# FTS_V1_0.net
KiCad netlist of a schematic drawn in EAGLE
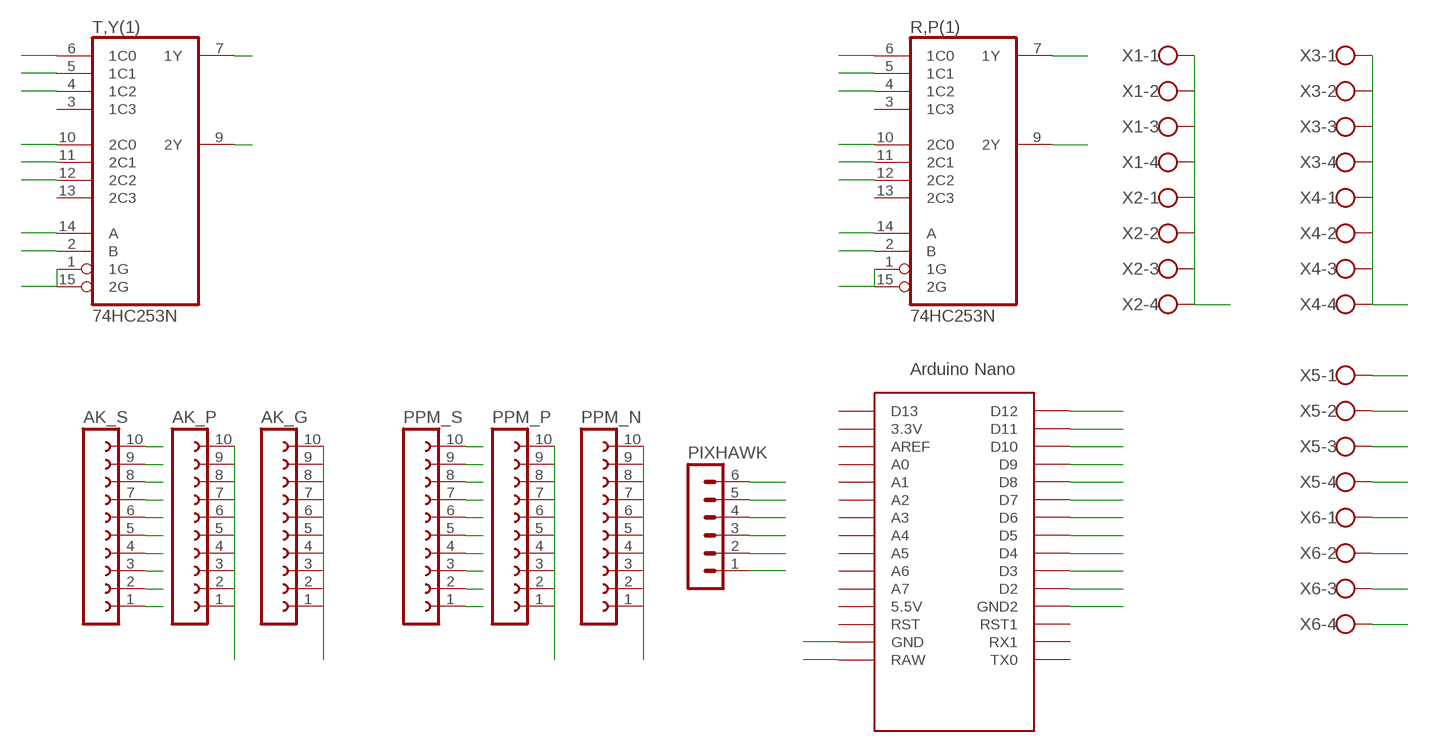
[diagram p0: schematic, sheet 1]

(export (version "E")
  (design (tool "Eeschema 10.0.6"))
  (components
    (comp (ref "AK_G")
      (value "FE10-1")
      (footprint "eagle-import:FE10")
      (libsource (lib "eagle-import") (part "FE10-1"))
    )
    (comp (ref "AK_P")
      (value "FE10-1")
      (footprint "eagle-import:FE10")
      (libsource (lib "eagle-import") (part "FE10-1"))
    )
    (comp (ref "AK_S")
      (value "FE10-1")
      (footprint "eagle-import:FE10")
      (libsource (lib "eagle-import") (part "FE10-1"))
    )
    (comp (ref "PIXHAWK")
      (value "MA06-1")
      (footprint "eagle-import:MA06-1")
      (libsource (lib "eagle-import") (part "MA06-1"))
    )
    (comp (ref "PPM_N")
      (value "FE10-1")
      (footprint "eagle-import:FE10")
      (libsource (lib "eagle-import") (part "FE10-1"))
    )
    (comp (ref "PPM_P")
      (value "FE10-1")
      (footprint "eagle-import:FE10")
      (libsource (lib "eagle-import") (part "FE10-1"))
    )
    (comp (ref "PPM_S")
      (value "FE10-1")
      (footprint "eagle-import:FE10")
      (libsource (lib "eagle-import") (part "FE10-1"))
    )
    (comp (ref "R,P(1)")
      (value "74HC253N")
      (footprint "eagle-import:DIL16")
      (libsource (lib "eagle-import") (part "74253NHC"))
    )
    (comp (ref "T,Y(1)")
      (value "74HC253N")
      (footprint "eagle-import:DIL16")
      (libsource (lib "eagle-import") (part "74253NHC"))
    )
    (comp (ref "U$1")
      (value "NANO")
      (footprint "eagle-import:NANO")
      (libsource (lib "eagle-import") (part "NANO"))
    )
    (comp (ref "X1")
      (value "W237-4")
      (footprint "eagle-import:W237-4")
      (libsource (lib "eagle-import") (part "W237-4"))
    )
    (comp (ref "X2")
      (value "W237-4")
      (footprint "eagle-import:W237-4")
      (libsource (lib "eagle-import") (part "W237-4"))
    )
    (comp (ref "X3")
      (value "W237-4")
      (footprint "eagle-import:W237-4")
      (libsource (lib "eagle-import") (part "W237-4"))
    )
    (comp (ref "X4")
      (value "W237-4")
      (footprint "eagle-import:W237-4")
      (libsource (lib "eagle-import") (part "W237-4"))
    )
    (comp (ref "X5")
      (value "W237-4")
      (footprint "eagle-import:W237-4")
      (libsource (lib "eagle-import") (part "W237-4"))
    )
    (comp (ref "X6")
      (value "W237-4")
      (footprint "eagle-import:W237-4")
      (libsource (lib "eagle-import") (part "W237-4"))
    )
  )
  (nets
    (net (code "1") (name "/AUX2") (class "Default")
      (node (ref "AK_S") (pin "7") (pinfunction "7_7") (pintype "passive"))
      (node (ref "U$1") (pin "D4") (pinfunction "D4_D4") (pintype "bidirectional"))
    )
    (net (code "2") (name "/DROP") (class "Default")
      (node (ref "AK_S") (pin "10") (pinfunction "10_10") (pintype "passive"))
      (node (ref "X6") (pin "4") (pinfunction "KL_4") (pintype "passive"))
    )
    (net (code "3") (name "/FTS-P") (class "Default")
      (node (ref "R,P(1)") (pin "12") (pinfunction "2C2_12") (pintype "input"))
      (node (ref "U$1") (pin "D10") (pinfunction "D10_D10") (pintype "bidirectional"))
    )
    (net (code "4") (name "/FTS-R") (class "Default")
      (node (ref "R,P(1)") (pin "4") (pinfunction "1C2_4") (pintype "input"))
      (node (ref "U$1") (pin "D9") (pinfunction "D9_D9") (pintype "bidirectional"))
    )
    (net (code "5") (name "/FTS-T") (class "Default")
      (node (ref "T,Y(1)") (pin "4") (pinfunction "1C2_4") (pintype "input"))
      (node (ref "U$1") (pin "D11") (pinfunction "D11_D11") (pintype "bidirectional"))
    )
    (net (code "6") (name "/FTS-Y") (class "Default")
      (node (ref "T,Y(1)") (pin "12") (pinfunction "2C2_12") (pintype "input"))
      (node (ref "U$1") (pin "D6") (pinfunction "D6_D6") (pintype "bidirectional"))
    )
    (net (code "7") (name "/GBL-P") (class "Default")
      (node (ref "AK_S") (pin "9") (pinfunction "9_9") (pintype "passive"))
      (node (ref "X6") (pin "3") (pinfunction "KL_3") (pintype "passive"))
    )
    (net (code "8") (name "/GBL-R") (class "Default")
      (node (ref "AK_S") (pin "8") (pinfunction "8_8") (pintype "passive"))
      (node (ref "X6") (pin "2") (pinfunction "KL_2") (pintype "passive"))
    )
    (net (code "9") (name "/GEAR") (class "Default")
      (node (ref "AK_S") (pin "6") (pinfunction "6_6") (pintype "passive"))
      (node (ref "U$1") (pin "D5") (pinfunction "D5_D5") (pintype "bidirectional"))
    )
    (net (code "10") (name "/GND") (class "Default")
      (node (ref "AK_G") (pin "1") (pinfunction "1_1") (pintype "passive"))
      (node (ref "AK_G") (pin "10") (pinfunction "10_10") (pintype "passive"))
      (node (ref "AK_G") (pin "2") (pinfunction "2_2") (pintype "passive"))
      (node (ref "AK_G") (pin "3") (pinfunction "3_3") (pintype "passive"))
      (node (ref "AK_G") (pin "4") (pinfunction "4_4") (pintype "passive"))
      (node (ref "AK_G") (pin "5") (pinfunction "5_5") (pintype "passive"))
      (node (ref "AK_G") (pin "6") (pinfunction "6_6") (pintype "passive"))
      (node (ref "AK_G") (pin "7") (pinfunction "7_7") (pintype "passive"))
      (node (ref "AK_G") (pin "8") (pinfunction "8_8") (pintype "passive"))
      (node (ref "AK_G") (pin "9") (pinfunction "9_9") (pintype "passive"))
      (node (ref "PIXHAWK") (pin "6") (pinfunction "6_6") (pintype "passive"))
      (node (ref "PPM_N") (pin "1") (pinfunction "1_1") (pintype "passive"))
      (node (ref "PPM_N") (pin "10") (pinfunction "10_10") (pintype "passive"))
      (node (ref "PPM_N") (pin "2") (pinfunction "2_2") (pintype "passive"))
      (node (ref "PPM_N") (pin "3") (pinfunction "3_3") (pintype "passive"))
      (node (ref "PPM_N") (pin "4") (pinfunction "4_4") (pintype "passive"))
      (node (ref "PPM_N") (pin "5") (pinfunction "5_5") (pintype "passive"))
      (node (ref "PPM_N") (pin "6") (pinfunction "6_6") (pintype "passive"))
      (node (ref "PPM_N") (pin "7") (pinfunction "7_7") (pintype "passive"))
      (node (ref "PPM_N") (pin "8") (pinfunction "8_8") (pintype "passive"))
      (node (ref "PPM_N") (pin "9") (pinfunction "9_9") (pintype "passive"))
      (node (ref "R,P(1)") (pin "1") (pinfunction "1G_1") (pintype "input"))
      (node (ref "R,P(1)") (pin "15") (pinfunction "2G_15") (pintype "input"))
      (node (ref "T,Y(1)") (pin "1") (pinfunction "1G_1") (pintype "input"))
      (node (ref "T,Y(1)") (pin "15") (pinfunction "2G_15") (pintype "input"))
      (node (ref "U$1") (pin "GND") (pinfunction "GND_GND") (pintype "bidirectional"))
      (node (ref "U$1") (pin "GND1") (pinfunction "GND2_GND1") (pintype "bidirectional"))
      (node (ref "X3") (pin "1") (pinfunction "KL_1") (pintype "passive"))
      (node (ref "X3") (pin "2") (pinfunction "KL_2") (pintype "passive"))
      (node (ref "X3") (pin "3") (pinfunction "KL_3") (pintype "passive"))
      (node (ref "X3") (pin "4") (pinfunction "KL_4") (pintype "passive"))
      (node (ref "X4") (pin "1") (pinfunction "KL_1") (pintype "passive"))
      (node (ref "X4") (pin "2") (pinfunction "KL_2") (pintype "passive"))
      (node (ref "X4") (pin "3") (pinfunction "KL_3") (pintype "passive"))
      (node (ref "X4") (pin "4") (pinfunction "KL_4") (pintype "passive"))
    )
    (net (code "11") (name "/PPM_FM") (class "Default")
      (node (ref "PPM_S") (pin "5") (pinfunction "5_5") (pintype "passive"))
      (node (ref "U$1") (pin "D8") (pinfunction "D8_D8") (pintype "bidirectional"))
    )
    (net (code "12") (name "/PX-P") (class "Default")
      (node (ref "PIXHAWK") (pin "2") (pinfunction "2_2") (pintype "passive"))
      (node (ref "R,P(1)") (pin "11") (pinfunction "2C1_11") (pintype "input"))
    )
    (net (code "13") (name "/PX-R") (class "Default")
      (node (ref "PIXHAWK") (pin "1") (pinfunction "1_1") (pintype "passive"))
      (node (ref "R,P(1)") (pin "5") (pinfunction "1C1_5") (pintype "input"))
    )
    (net (code "14") (name "/PX-T") (class "Default")
      (node (ref "PIXHAWK") (pin "3") (pinfunction "3_3") (pintype "passive"))
      (node (ref "T,Y(1)") (pin "5") (pinfunction "1C1_5") (pintype "input"))
    )
    (net (code "15") (name "/PX-Y") (class "Default")
      (node (ref "PIXHAWK") (pin "4") (pinfunction "4_4") (pintype "passive"))
      (node (ref "T,Y(1)") (pin "11") (pinfunction "2C1_11") (pintype "input"))
    )
    (net (code "16") (name "/RX-FM") (class "Default")
      (node (ref "AK_S") (pin "5") (pinfunction "5_5") (pintype "passive"))
      (node (ref "U$1") (pin "D7") (pinfunction "D7_D7") (pintype "bidirectional"))
    )
    (net (code "17") (name "/RX-P") (class "Default")
      (node (ref "AK_S") (pin "2") (pinfunction "2_2") (pintype "passive"))
      (node (ref "PPM_S") (pin "2") (pinfunction "2_2") (pintype "passive"))
      (node (ref "R,P(1)") (pin "10") (pinfunction "2C0_10") (pintype "input"))
    )
    (net (code "18") (name "/RX-R") (class "Default")
      (node (ref "AK_S") (pin "1") (pinfunction "1_1") (pintype "passive"))
      (node (ref "PPM_S") (pin "1") (pinfunction "1_1") (pintype "passive"))
      (node (ref "R,P(1)") (pin "6") (pinfunction "1C0_6") (pintype "input"))
    )
    (net (code "19") (name "/RX-T") (class "Default")
      (node (ref "AK_S") (pin "3") (pinfunction "3_3") (pintype "passive"))
      (node (ref "PPM_S") (pin "3") (pinfunction "3_3") (pintype "passive"))
      (node (ref "T,Y(1)") (pin "6") (pinfunction "1C0_6") (pintype "input"))
      (node (ref "U$1") (pin "D12") (pinfunction "D12_D12") (pintype "bidirectional"))
    )
    (net (code "20") (name "/RX-Y") (class "Default")
      (node (ref "AK_S") (pin "4") (pinfunction "4_4") (pintype "passive"))
      (node (ref "PPM_S") (pin "4") (pinfunction "4_4") (pintype "passive"))
      (node (ref "T,Y(1)") (pin "10") (pinfunction "2C0_10") (pintype "input"))
    )
    (net (code "21") (name "/S-P") (class "Default")
      (node (ref "R,P(1)") (pin "9") (pinfunction "2Y_9") (pintype "tri_state"))
      (node (ref "X5") (pin "2") (pinfunction "KL_2") (pintype "passive"))
    )
    (net (code "22") (name "/S-R") (class "Default")
      (node (ref "R,P(1)") (pin "7") (pinfunction "1Y_7") (pintype "tri_state"))
      (node (ref "X5") (pin "1") (pinfunction "KL_1") (pintype "passive"))
    )
    (net (code "23") (name "/S-T") (class "Default")
      (node (ref "T,Y(1)") (pin "7") (pinfunction "1Y_7") (pintype "tri_state"))
      (node (ref "X5") (pin "3") (pinfunction "KL_3") (pintype "passive"))
    )
    (net (code "24") (name "/S-Y") (class "Default")
      (node (ref "T,Y(1)") (pin "9") (pinfunction "2Y_9") (pintype "tri_state"))
      (node (ref "X5") (pin "4") (pinfunction "KL_4") (pintype "passive"))
      (node (ref "X6") (pin "1") (pinfunction "KL_1") (pintype "passive"))
    )
    (net (code "25") (name "/S1") (class "Default")
      (node (ref "R,P(1)") (pin "14") (pinfunction "A_14") (pintype "input"))
      (node (ref "T,Y(1)") (pin "14") (pinfunction "A_14") (pintype "input"))
      (node (ref "U$1") (pin "D2") (pinfunction "D2_D2") (pintype "bidirectional"))
    )
    (net (code "26") (name "/S2") (class "Default")
      (node (ref "R,P(1)") (pin "2") (pinfunction "B_2") (pintype "input"))
      (node (ref "T,Y(1)") (pin "2") (pinfunction "B_2") (pintype "input"))
      (node (ref "U$1") (pin "D3") (pinfunction "D3_D3") (pintype "bidirectional"))
    )
    (net (code "27") (name "/VCC") (class "Default")
      (node (ref "AK_P") (pin "1") (pinfunction "1_1") (pintype "passive"))
      (node (ref "AK_P") (pin "10") (pinfunction "10_10") (pintype "passive"))
      (node (ref "AK_P") (pin "2") (pinfunction "2_2") (pintype "passive"))
      (node (ref "AK_P") (pin "3") (pinfunction "3_3") (pintype "passive"))
      (node (ref "AK_P") (pin "4") (pinfunction "4_4") (pintype "passive"))
      (node (ref "AK_P") (pin "5") (pinfunction "5_5") (pintype "passive"))
      (node (ref "AK_P") (pin "6") (pinfunction "6_6") (pintype "passive"))
      (node (ref "AK_P") (pin "7") (pinfunction "7_7") (pintype "passive"))
      (node (ref "AK_P") (pin "8") (pinfunction "8_8") (pintype "passive"))
      (node (ref "AK_P") (pin "9") (pinfunction "9_9") (pintype "passive"))
      (node (ref "PPM_P") (pin "1") (pinfunction "1_1") (pintype "passive"))
      (node (ref "PPM_P") (pin "10") (pinfunction "10_10") (pintype "passive"))
      (node (ref "PPM_P") (pin "2") (pinfunction "2_2") (pintype "passive"))
      (node (ref "PPM_P") (pin "3") (pinfunction "3_3") (pintype "passive"))
      (node (ref "PPM_P") (pin "4") (pinfunction "4_4") (pintype "passive"))
      (node (ref "PPM_P") (pin "5") (pinfunction "5_5") (pintype "passive"))
      (node (ref "PPM_P") (pin "6") (pinfunction "6_6") (pintype "passive"))
      (node (ref "PPM_P") (pin "7") (pinfunction "7_7") (pintype "passive"))
      (node (ref "PPM_P") (pin "8") (pinfunction "8_8") (pintype "passive"))
      (node (ref "PPM_P") (pin "9") (pinfunction "9_9") (pintype "passive"))
      (node (ref "U$1") (pin "RAW") (pinfunction "RAW_RAW") (pintype "bidirectional"))
      (node (ref "X1") (pin "1") (pinfunction "KL_1") (pintype "passive"))
      (node (ref "X1") (pin "2") (pinfunction "KL_2") (pintype "passive"))
      (node (ref "X1") (pin "3") (pinfunction "KL_3") (pintype "passive"))
      (node (ref "X1") (pin "4") (pinfunction "KL_4") (pintype "passive"))
      (node (ref "X2") (pin "1") (pinfunction "KL_1") (pintype "passive"))
      (node (ref "X2") (pin "2") (pinfunction "KL_2") (pintype "passive"))
      (node (ref "X2") (pin "3") (pinfunction "KL_3") (pintype "passive"))
      (node (ref "X2") (pin "4") (pinfunction "KL_4") (pintype "passive"))
    )
    (net (code "28") (name "unconnected-(PIXHAWK-Pad5)") (class "Default")
      (node (ref "PIXHAWK") (pin "5") (pinfunction "5_5") (pintype "passive"))
    )
    (net (code "29") (name "unconnected-(PPM_S-Pad6)") (class "Default")
      (node (ref "PPM_S") (pin "6") (pinfunction "6_6") (pintype "passive"))
    )
    (net (code "30") (name "unconnected-(PPM_S-Pad7)") (class "Default")
      (node (ref "PPM_S") (pin "7") (pinfunction "7_7") (pintype "passive"))
    )
    (net (code "31") (name "unconnected-(PPM_S-Pad8)") (class "Default")
      (node (ref "PPM_S") (pin "8") (pinfunction "8_8") (pintype "passive"))
    )
    (net (code "32") (name "unconnected-(PPM_S-Pad9)") (class "Default")
      (node (ref "PPM_S") (pin "9") (pinfunction "9_9") (pintype "passive"))
    )
    (net (code "33") (name "unconnected-(PPM_S-Pad10)") (class "Default")
      (node (ref "PPM_S") (pin "10") (pinfunction "10_10") (pintype "passive"))
    )
    (net (code "34") (name "unconnected-(R,P(1)A-1C3-Pad3)") (class "Default")
      (node (ref "R,P(1)") (pin "3") (pinfunction "1C3_3") (pintype "input"))
    )
    (net (code "35") (name "unconnected-(R,P(1)A-2C3-Pad13)") (class "Default")
      (node (ref "R,P(1)") (pin "13") (pinfunction "2C3_13") (pintype "input"))
    )
    (net (code "36") (name "unconnected-(T,Y(1)A-1C3-Pad3)") (class "Default")
      (node (ref "T,Y(1)") (pin "3") (pinfunction "1C3_3") (pintype "input"))
    )
    (net (code "37") (name "unconnected-(T,Y(1)A-2C3-Pad13)") (class "Default")
      (node (ref "T,Y(1)") (pin "13") (pinfunction "2C3_13") (pintype "input"))
    )
    (net (code "38") (name "unconnected-(U$1-5.5V-Pad5V)") (class "Default")
      (node (ref "U$1") (pin "5V") (pinfunction "5.5V_5V") (pintype "bidirectional"))
    )
    (net (code "39") (name "unconnected-(U$1-Pad3.3V)") (class "Default")
      (node (ref "U$1") (pin "3.3V") (pinfunction "3.3V_3.3V") (pintype "bidirectional"))
    )
    (net (code "40") (name "unconnected-(U$1-PadA0)") (class "Default")
      (node (ref "U$1") (pin "A0") (pinfunction "A0_A0") (pintype "bidirectional"))
    )
    (net (code "41") (name "unconnected-(U$1-PadA1)") (class "Default")
      (node (ref "U$1") (pin "A1") (pinfunction "A1_A1") (pintype "bidirectional"))
    )
    (net (code "42") (name "unconnected-(U$1-PadA2)") (class "Default")
      (node (ref "U$1") (pin "A2") (pinfunction "A2_A2") (pintype "bidirectional"))
    )
    (net (code "43") (name "unconnected-(U$1-PadA3)") (class "Default")
      (node (ref "U$1") (pin "A3") (pinfunction "A3_A3") (pintype "bidirectional"))
    )
    (net (code "44") (name "unconnected-(U$1-PadA4)") (class "Default")
      (node (ref "U$1") (pin "A4") (pinfunction "A4_A4") (pintype "bidirectional"))
    )
    (net (code "45") (name "unconnected-(U$1-PadA5)") (class "Default")
      (node (ref "U$1") (pin "A5") (pinfunction "A5_A5") (pintype "bidirectional"))
    )
    (net (code "46") (name "unconnected-(U$1-PadA6)") (class "Default")
      (node (ref "U$1") (pin "A6") (pinfunction "A6_A6") (pintype "bidirectional"))
    )
    (net (code "47") (name "unconnected-(U$1-PadA7)") (class "Default")
      (node (ref "U$1") (pin "A7") (pinfunction "A7_A7") (pintype "bidirectional"))
    )
    (net (code "48") (name "unconnected-(U$1-PadAREF)") (class "Default")
      (node (ref "U$1") (pin "AREF") (pinfunction "AREF_AREF") (pintype "bidirectional"))
    )
    (net (code "49") (name "unconnected-(U$1-PadD13)") (class "Default")
      (node (ref "U$1") (pin "D13") (pinfunction "D13_D13") (pintype "bidirectional"))
    )
    (net (code "50") (name "unconnected-(U$1-PadICSP1)") (class "Default")
      (node (ref "U$1") (pin "ICSP1") (pinfunction "ICSP1_ICSP1") (pintype "bidirectional"))
    )
    (net (code "51") (name "unconnected-(U$1-PadICSP2)") (class "Default")
      (node (ref "U$1") (pin "ICSP2") (pinfunction "ICSP2_ICSP2") (pintype "bidirectional"))
    )
    (net (code "52") (name "unconnected-(U$1-PadICSP3)") (class "Default")
      (node (ref "U$1") (pin "ICSP3") (pinfunction "ICSP3_ICSP3") (pintype "bidirectional"))
    )
    (net (code "53") (name "unconnected-(U$1-PadICSP4)") (class "Default")
      (node (ref "U$1") (pin "ICSP4") (pinfunction "ICSP4_ICSP4") (pintype "bidirectional"))
    )
    (net (code "54") (name "unconnected-(U$1-PadICSP5)") (class "Default")
      (node (ref "U$1") (pin "ICSP5") (pinfunction "ICSP5_ICSP5") (pintype "bidirectional"))
    )
    (net (code "55") (name "unconnected-(U$1-PadICSP6)") (class "Default")
      (node (ref "U$1") (pin "ICSP6") (pinfunction "ICSP6_ICSP6") (pintype "bidirectional"))
    )
    (net (code "56") (name "unconnected-(U$1-PadRST)") (class "Default")
      (node (ref "U$1") (pin "RST") (pinfunction "RST_RST") (pintype "bidirectional"))
    )
    (net (code "57") (name "unconnected-(U$1-PadRST1)") (class "Default")
      (node (ref "U$1") (pin "RST1") (pinfunction "RST1_RST1") (pintype "bidirectional"))
    )
    (net (code "58") (name "unconnected-(U$1-PadRX1)") (class "Default")
      (node (ref "U$1") (pin "RX1") (pinfunction "RX1_RX1") (pintype "bidirectional"))
    )
    (net (code "59") (name "unconnected-(U$1-PadTX0)") (class "Default")
      (node (ref "U$1") (pin "TX0") (pinfunction "TX0_TX0") (pintype "bidirectional"))
    )
  )
)
